# avr-isp-breakout-board.net
KiCad netlist of a schematic drawn in EAGLE
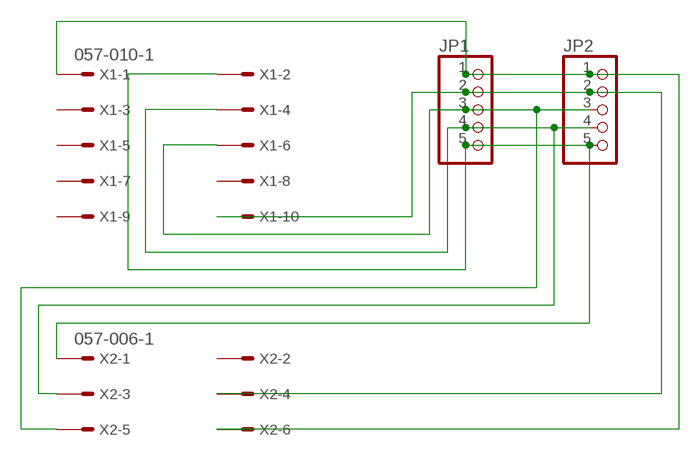
[diagram p0: schematic, sheet 1]

(export (version "E")
  (design (tool "Eeschema 10.0.6"))
  (components
    (comp (ref "JP1")
      (value "PINHD-1X5")
      (footprint "eagle-import:1X05")
      (libsource (lib "eagle-import") (part "PINHD-1X5"))
    )
    (comp (ref "JP2")
      (value "PINHD-1X5")
      (footprint "eagle-import:1X05")
      (libsource (lib "eagle-import") (part "PINHD-1X5"))
    )
    (comp (ref "X1")
      (value "057-010-1")
      (footprint "eagle-import:057-010-1")
      (libsource (lib "eagle-import") (part "057-010-1"))
    )
    (comp (ref "X2")
      (value "057-006-1")
      (footprint "eagle-import:057-006-1")
      (libsource (lib "eagle-import") (part "057-006-1"))
    )
  )
  (nets
    (net (code "1") (name "Net-(X1A-S)") (class "Default")
      (node (ref "JP1") (pin "1") (pinfunction "1_1") (pintype "passive"))
      (node (ref "JP2") (pin "1") (pinfunction "1_1") (pintype "passive"))
      (node (ref "X1") (pin "1") (pinfunction "S_1") (pintype "passive"))
      (node (ref "X2") (pin "6") (pinfunction "S_6") (pintype "passive"))
    )
    (net (code "2") (name "Net-(X1B-S)") (class "Default")
      (node (ref "JP1") (pin "2") (pinfunction "2_2") (pintype "passive"))
      (node (ref "JP2") (pin "2") (pinfunction "2_2") (pintype "passive"))
      (node (ref "X1") (pin "10") (pinfunction "S_10") (pintype "passive"))
      (node (ref "X2") (pin "4") (pinfunction "S_4") (pintype "passive"))
    )
    (net (code "3") (name "Net-(X1C-S)") (class "Default")
      (node (ref "JP1") (pin "5") (pinfunction "5_5") (pintype "passive"))
      (node (ref "JP2") (pin "5") (pinfunction "5_5") (pintype "passive"))
      (node (ref "X1") (pin "2") (pinfunction "S_2") (pintype "passive"))
      (node (ref "X2") (pin "1") (pinfunction "S_1") (pintype "passive"))
    )
    (net (code "4") (name "Net-(X1E-S)") (class "Default")
      (node (ref "JP1") (pin "4") (pinfunction "4_4") (pintype "passive"))
      (node (ref "JP2") (pin "4") (pinfunction "4_4") (pintype "passive"))
      (node (ref "X1") (pin "4") (pinfunction "S_4") (pintype "passive"))
      (node (ref "X2") (pin "3") (pinfunction "S_3") (pintype "passive"))
    )
    (net (code "5") (name "Net-(X1G-S)") (class "Default")
      (node (ref "JP1") (pin "3") (pinfunction "3_3") (pintype "passive"))
      (node (ref "JP2") (pin "3") (pinfunction "3_3") (pintype "passive"))
      (node (ref "X1") (pin "6") (pinfunction "S_6") (pintype "passive"))
      (node (ref "X2") (pin "5") (pinfunction "S_5") (pintype "passive"))
    )
    (net (code "6") (name "unconnected-(X1D-S-Pad3)") (class "Default")
      (node (ref "X1") (pin "3") (pinfunction "S_3") (pintype "passive"))
    )
    (net (code "7") (name "unconnected-(X1F-S-Pad5)") (class "Default")
      (node (ref "X1") (pin "5") (pinfunction "S_5") (pintype "passive"))
    )
    (net (code "8") (name "unconnected-(X1H-S-Pad7)") (class "Default")
      (node (ref "X1") (pin "7") (pinfunction "S_7") (pintype "passive"))
    )
    (net (code "9") (name "unconnected-(X1I-S-Pad8)") (class "Default")
      (node (ref "X1") (pin "8") (pinfunction "S_8") (pintype "passive"))
    )
    (net (code "10") (name "unconnected-(X1J-S-Pad9)") (class "Default")
      (node (ref "X1") (pin "9") (pinfunction "S_9") (pintype "passive"))
    )
    (net (code "11") (name "unconnected-(X2B-S-Pad2)") (class "Default")
      (node (ref "X2") (pin "2") (pinfunction "S_2") (pintype "passive"))
    )
  )
)
